# MEMC_Plug_FFC.net
KiCad netlist of a schematic drawn in Altium Designer
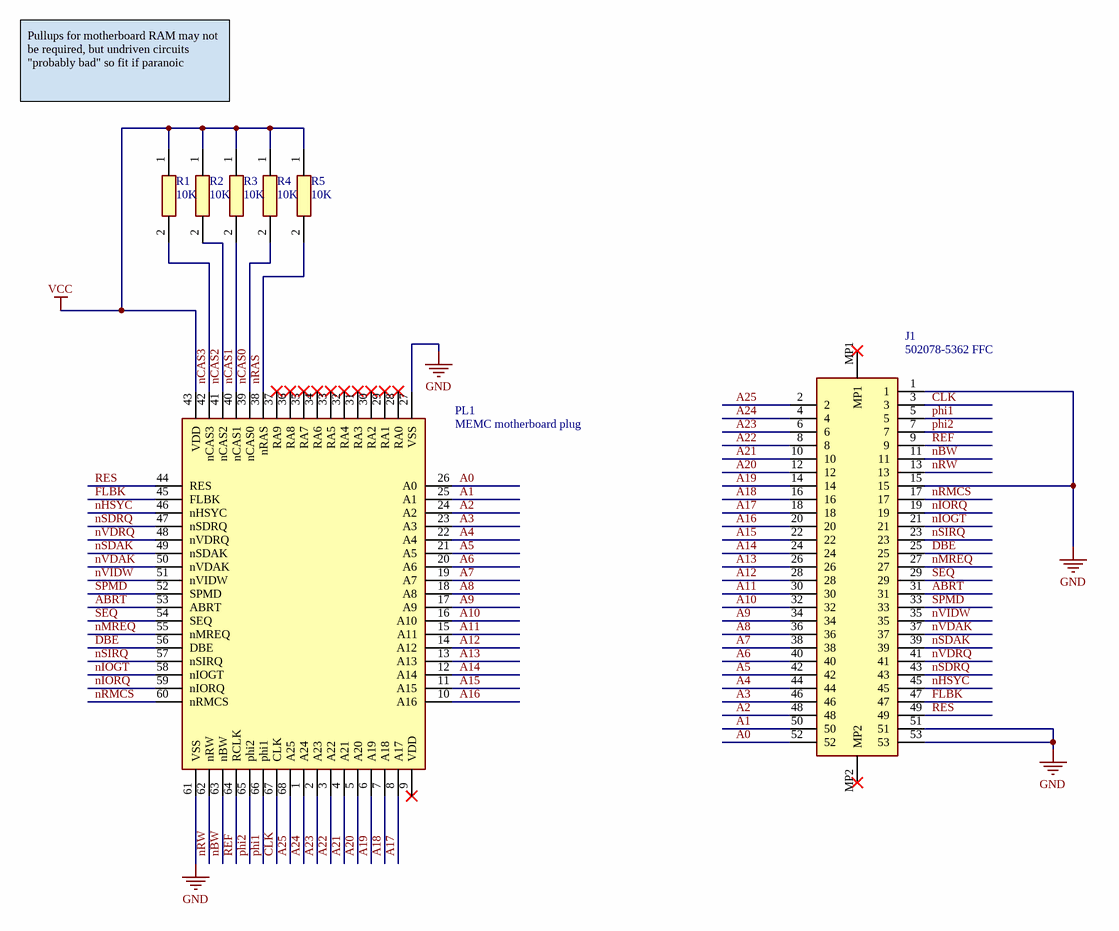
[diagram p0: MEMC_Plug_FFC.SchDoc]

(export (version "E")
  (design (tool "Eeschema 10.0.6"))
  (components
    (comp (ref "J1")
      (value "502078-5362 FFC")
      (footprint "SamacSys:5020785362")
      (description "Connector")
      (fields
        (field (name "MANUFACTURER_PART_NUMBER") "502078-5362")
        (field (name "MOUSER PART NUMBER") "538-502078-5362")
      )
      (libsource (lib "*") (part "502078-5362"))
    )
    (comp (ref "PL1")
      (value "MEMC motherboard plug")
      (footprint "MEMC_Plug")
      (description "MEMC plug")
      (libsource (lib "Acorn") (part "MEMC_Plug"))
    )
    (comp (ref "R1")
      (value "10K")
      (footprint "SamacSys:RESC1005X40N")
      (description "Resistor")
      (fields
        (field (name "MANUFACTURER_PART_NUMBER") "CRCW040210K0FKEDHP")
        (field (name "MOUSER PART NUMBER") "71-CRCW040210K0FKEDH")
      )
      (libsource (lib "*") (part "CRCW040210K0FKEDHP"))
    )
    (comp (ref "R2")
      (value "10K")
      (footprint "SamacSys:RESC1005X40N")
      (description "Resistor")
      (fields
        (field (name "MANUFACTURER_PART_NUMBER") "CRCW040210K0FKEDHP")
        (field (name "MOUSER PART NUMBER") "71-CRCW040210K0FKEDH")
      )
      (libsource (lib "*") (part "CRCW040210K0FKEDHP"))
    )
    (comp (ref "R3")
      (value "10K")
      (footprint "SamacSys:RESC1005X40N")
      (description "Resistor")
      (fields
        (field (name "MANUFACTURER_PART_NUMBER") "CRCW040210K0FKEDHP")
        (field (name "MOUSER PART NUMBER") "71-CRCW040210K0FKEDH")
      )
      (libsource (lib "*") (part "CRCW040210K0FKEDHP"))
    )
    (comp (ref "R4")
      (value "10K")
      (footprint "SamacSys:RESC1005X40N")
      (description "Resistor")
      (fields
        (field (name "MANUFACTURER_PART_NUMBER") "CRCW040210K0FKEDHP")
        (field (name "MOUSER PART NUMBER") "71-CRCW040210K0FKEDH")
      )
      (libsource (lib "*") (part "CRCW040210K0FKEDHP"))
    )
    (comp (ref "R5")
      (value "10K")
      (footprint "SamacSys:RESC1005X40N")
      (description "Resistor")
      (fields
        (field (name "MANUFACTURER_PART_NUMBER") "CRCW040210K0FKEDHP")
        (field (name "MOUSER PART NUMBER") "71-CRCW040210K0FKEDH")
      )
      (libsource (lib "*") (part "CRCW040210K0FKEDHP"))
    )
  )
  (nets
    (net (code "1") (name "/A0") (class "Default")
      (node (ref "J1") (pin "52") (pinfunction "52_52") (pintype "passive"))
      (node (ref "PL1") (pin "26") (pinfunction "A0_26") (pintype "passive"))
    )
    (net (code "2") (name "/A1") (class "Default")
      (node (ref "J1") (pin "50") (pinfunction "50_50") (pintype "passive"))
      (node (ref "PL1") (pin "25") (pinfunction "A1_25") (pintype "passive"))
    )
    (net (code "3") (name "/A2") (class "Default")
      (node (ref "J1") (pin "48") (pinfunction "48_48") (pintype "passive"))
      (node (ref "PL1") (pin "24") (pinfunction "A2_24") (pintype "passive"))
    )
    (net (code "4") (name "/A3") (class "Default")
      (node (ref "J1") (pin "46") (pinfunction "46_46") (pintype "passive"))
      (node (ref "PL1") (pin "23") (pinfunction "A3_23") (pintype "passive"))
    )
    (net (code "5") (name "/A4") (class "Default")
      (node (ref "J1") (pin "44") (pinfunction "44_44") (pintype "passive"))
      (node (ref "PL1") (pin "22") (pinfunction "A4_22") (pintype "passive"))
    )
    (net (code "6") (name "/A5") (class "Default")
      (node (ref "J1") (pin "42") (pinfunction "42_42") (pintype "passive"))
      (node (ref "PL1") (pin "21") (pinfunction "A5_21") (pintype "passive"))
    )
    (net (code "7") (name "/A6") (class "Default")
      (node (ref "J1") (pin "40") (pinfunction "40_40") (pintype "passive"))
      (node (ref "PL1") (pin "20") (pinfunction "A6_20") (pintype "passive"))
    )
    (net (code "8") (name "/A7") (class "Default")
      (node (ref "J1") (pin "38") (pinfunction "38_38") (pintype "passive"))
      (node (ref "PL1") (pin "19") (pinfunction "A7_19") (pintype "passive"))
    )
    (net (code "9") (name "/A8") (class "Default")
      (node (ref "J1") (pin "36") (pinfunction "36_36") (pintype "passive"))
      (node (ref "PL1") (pin "18") (pinfunction "A8_18") (pintype "passive"))
    )
    (net (code "10") (name "/A9") (class "Default")
      (node (ref "J1") (pin "34") (pinfunction "34_34") (pintype "passive"))
      (node (ref "PL1") (pin "17") (pinfunction "A9_17") (pintype "passive"))
    )
    (net (code "11") (name "/A10") (class "Default")
      (node (ref "J1") (pin "32") (pinfunction "32_32") (pintype "passive"))
      (node (ref "PL1") (pin "16") (pinfunction "A10_16") (pintype "passive"))
    )
    (net (code "12") (name "/A11") (class "Default")
      (node (ref "J1") (pin "30") (pinfunction "30_30") (pintype "passive"))
      (node (ref "PL1") (pin "15") (pinfunction "A11_15") (pintype "passive"))
    )
    (net (code "13") (name "/A12") (class "Default")
      (node (ref "J1") (pin "28") (pinfunction "28_28") (pintype "passive"))
      (node (ref "PL1") (pin "14") (pinfunction "A12_14") (pintype "passive"))
    )
    (net (code "14") (name "/A13") (class "Default")
      (node (ref "J1") (pin "26") (pinfunction "26_26") (pintype "passive"))
      (node (ref "PL1") (pin "13") (pinfunction "A13_13") (pintype "passive"))
    )
    (net (code "15") (name "/A14") (class "Default")
      (node (ref "J1") (pin "24") (pinfunction "24_24") (pintype "passive"))
      (node (ref "PL1") (pin "12") (pinfunction "A14_12") (pintype "passive"))
    )
    (net (code "16") (name "/A15") (class "Default")
      (node (ref "J1") (pin "22") (pinfunction "22_22") (pintype "passive"))
      (node (ref "PL1") (pin "11") (pinfunction "A15_11") (pintype "passive"))
    )
    (net (code "17") (name "/A16") (class "Default")
      (node (ref "J1") (pin "20") (pinfunction "20_20") (pintype "passive"))
      (node (ref "PL1") (pin "10") (pinfunction "A16_10") (pintype "passive"))
    )
    (net (code "18") (name "/A17") (class "Default")
      (node (ref "J1") (pin "18") (pinfunction "18_18") (pintype "passive"))
      (node (ref "PL1") (pin "8") (pinfunction "A17_8") (pintype "passive"))
    )
    (net (code "19") (name "/A18") (class "Default")
      (node (ref "J1") (pin "16") (pinfunction "16_16") (pintype "passive"))
      (node (ref "PL1") (pin "7") (pinfunction "A18_7") (pintype "passive"))
    )
    (net (code "20") (name "/A19") (class "Default")
      (node (ref "J1") (pin "14") (pinfunction "14_14") (pintype "passive"))
      (node (ref "PL1") (pin "6") (pinfunction "A19_6") (pintype "passive"))
    )
    (net (code "21") (name "/A20") (class "Default")
      (node (ref "J1") (pin "12") (pinfunction "12_12") (pintype "passive"))
      (node (ref "PL1") (pin "5") (pinfunction "A20_5") (pintype "passive"))
    )
    (net (code "22") (name "/A21") (class "Default")
      (node (ref "J1") (pin "10") (pinfunction "10_10") (pintype "passive"))
      (node (ref "PL1") (pin "4") (pinfunction "A21_4") (pintype "passive"))
    )
    (net (code "23") (name "/A22") (class "Default")
      (node (ref "J1") (pin "8") (pinfunction "8_8") (pintype "passive"))
      (node (ref "PL1") (pin "3") (pinfunction "A22_3") (pintype "passive"))
    )
    (net (code "24") (name "/A23") (class "Default")
      (node (ref "J1") (pin "6") (pinfunction "6_6") (pintype "passive"))
      (node (ref "PL1") (pin "2") (pinfunction "A23_2") (pintype "passive"))
    )
    (net (code "25") (name "/A24") (class "Default")
      (node (ref "J1") (pin "4") (pinfunction "4_4") (pintype "passive"))
      (node (ref "PL1") (pin "1") (pinfunction "A24_1") (pintype "passive"))
    )
    (net (code "26") (name "/A25") (class "Default")
      (node (ref "J1") (pin "2") (pinfunction "2_2") (pintype "passive"))
      (node (ref "PL1") (pin "68") (pinfunction "A25_68") (pintype "passive"))
    )
    (net (code "27") (name "/ABRT") (class "Default")
      (node (ref "J1") (pin "31") (pinfunction "31_31") (pintype "passive"))
      (node (ref "PL1") (pin "53") (pinfunction "ABRT_53") (pintype "passive"))
    )
    (net (code "28") (name "/CLK") (class "Default")
      (node (ref "J1") (pin "3") (pinfunction "3_3") (pintype "passive"))
      (node (ref "PL1") (pin "67") (pinfunction "CLK_67") (pintype "passive"))
    )
    (net (code "29") (name "/DBE") (class "Default")
      (node (ref "J1") (pin "25") (pinfunction "25_25") (pintype "passive"))
      (node (ref "PL1") (pin "56") (pinfunction "DBE_56") (pintype "passive"))
    )
    (net (code "30") (name "/FLBK") (class "Default")
      (node (ref "J1") (pin "47") (pinfunction "47_47") (pintype "passive"))
      (node (ref "PL1") (pin "45") (pinfunction "FLBK_45") (pintype "passive"))
    )
    (net (code "31") (name "/REF") (class "Default")
      (node (ref "J1") (pin "9") (pinfunction "9_9") (pintype "passive"))
      (node (ref "PL1") (pin "64") (pinfunction "RCLK_64") (pintype "passive"))
    )
    (net (code "32") (name "/RES") (class "Default")
      (node (ref "J1") (pin "49") (pinfunction "49_49") (pintype "passive"))
      (node (ref "PL1") (pin "44") (pinfunction "RES_44") (pintype "passive"))
    )
    (net (code "33") (name "/SEQ") (class "Default")
      (node (ref "J1") (pin "29") (pinfunction "29_29") (pintype "passive"))
      (node (ref "PL1") (pin "54") (pinfunction "SEQ_54") (pintype "passive"))
    )
    (net (code "34") (name "/SPMD") (class "Default")
      (node (ref "J1") (pin "33") (pinfunction "33_33") (pintype "passive"))
      (node (ref "PL1") (pin "52") (pinfunction "SPMD_52") (pintype "passive"))
    )
    (net (code "35") (name "/nBW") (class "Default")
      (node (ref "J1") (pin "11") (pinfunction "11_11") (pintype "passive"))
      (node (ref "PL1") (pin "63") (pinfunction "nBW_63") (pintype "passive"))
    )
    (net (code "36") (name "/nCAS0") (class "Default")
      (node (ref "PL1") (pin "39") (pinfunction "nCAS0_39") (pintype "passive"))
      (node (ref "R4") (pin "2") (pinfunction "2_2") (pintype "passive"))
    )
    (net (code "37") (name "/nCAS1") (class "Default")
      (node (ref "PL1") (pin "40") (pinfunction "nCAS1_40") (pintype "passive"))
      (node (ref "R3") (pin "2") (pinfunction "2_2") (pintype "passive"))
    )
    (net (code "38") (name "/nCAS2") (class "Default")
      (node (ref "PL1") (pin "41") (pinfunction "nCAS2_41") (pintype "passive"))
      (node (ref "R2") (pin "2") (pinfunction "2_2") (pintype "passive"))
    )
    (net (code "39") (name "/nCAS3") (class "Default")
      (node (ref "PL1") (pin "42") (pinfunction "nCAS3_42") (pintype "passive"))
      (node (ref "R1") (pin "2") (pinfunction "2_2") (pintype "passive"))
    )
    (net (code "40") (name "/nHSYC") (class "Default")
      (node (ref "J1") (pin "45") (pinfunction "45_45") (pintype "passive"))
      (node (ref "PL1") (pin "46") (pinfunction "nHSYC_46") (pintype "passive"))
    )
    (net (code "41") (name "/nIOGT") (class "Default")
      (node (ref "J1") (pin "21") (pinfunction "21_21") (pintype "passive"))
      (node (ref "PL1") (pin "58") (pinfunction "nIOGT_58") (pintype "passive"))
    )
    (net (code "42") (name "/nIORQ") (class "Default")
      (node (ref "J1") (pin "19") (pinfunction "19_19") (pintype "passive"))
      (node (ref "PL1") (pin "59") (pinfunction "nIORQ_59") (pintype "passive"))
    )
    (net (code "43") (name "/nMREQ") (class "Default")
      (node (ref "J1") (pin "27") (pinfunction "27_27") (pintype "passive"))
      (node (ref "PL1") (pin "55") (pinfunction "nMREQ_55") (pintype "passive"))
    )
    (net (code "44") (name "/nRAS") (class "Default")
      (node (ref "PL1") (pin "38") (pinfunction "nRAS_38") (pintype "passive"))
      (node (ref "R5") (pin "2") (pinfunction "2_2") (pintype "passive"))
    )
    (net (code "45") (name "/nRMCS") (class "Default")
      (node (ref "J1") (pin "17") (pinfunction "17_17") (pintype "passive"))
      (node (ref "PL1") (pin "60") (pinfunction "nRMCS_60") (pintype "passive"))
    )
    (net (code "46") (name "/nRW") (class "Default")
      (node (ref "J1") (pin "13") (pinfunction "13_13") (pintype "passive"))
      (node (ref "PL1") (pin "62") (pinfunction "nRW_62") (pintype "passive"))
    )
    (net (code "47") (name "/nSDAK") (class "Default")
      (node (ref "J1") (pin "39") (pinfunction "39_39") (pintype "passive"))
      (node (ref "PL1") (pin "49") (pinfunction "nSDAK_49") (pintype "passive"))
    )
    (net (code "48") (name "/nSDRQ") (class "Default")
      (node (ref "J1") (pin "43") (pinfunction "43_43") (pintype "passive"))
      (node (ref "PL1") (pin "47") (pinfunction "nSDRQ_47") (pintype "passive"))
    )
    (net (code "49") (name "/nSIRQ") (class "Default")
      (node (ref "J1") (pin "23") (pinfunction "23_23") (pintype "passive"))
      (node (ref "PL1") (pin "57") (pinfunction "nSIRQ_57") (pintype "passive"))
    )
    (net (code "50") (name "/nVDAK") (class "Default")
      (node (ref "J1") (pin "37") (pinfunction "37_37") (pintype "passive"))
      (node (ref "PL1") (pin "50") (pinfunction "nVDAK_50") (pintype "passive"))
    )
    (net (code "51") (name "/nVDRQ") (class "Default")
      (node (ref "J1") (pin "41") (pinfunction "41_41") (pintype "passive"))
      (node (ref "PL1") (pin "48") (pinfunction "nVDRQ_48") (pintype "passive"))
    )
    (net (code "52") (name "/nVIDW") (class "Default")
      (node (ref "J1") (pin "35") (pinfunction "35_35") (pintype "passive"))
      (node (ref "PL1") (pin "51") (pinfunction "nVIDW_51") (pintype "passive"))
    )
    (net (code "53") (name "/phi1") (class "Default")
      (node (ref "J1") (pin "5") (pinfunction "5_5") (pintype "passive"))
      (node (ref "PL1") (pin "66") (pinfunction "phi1_66") (pintype "passive"))
    )
    (net (code "54") (name "/phi2") (class "Default")
      (node (ref "J1") (pin "7") (pinfunction "7_7") (pintype "passive"))
      (node (ref "PL1") (pin "65") (pinfunction "phi2_65") (pintype "passive"))
    )
    (net (code "55") (name "GND") (class "Default")
      (node (ref "J1") (pin "1") (pinfunction "1_1") (pintype "passive"))
      (node (ref "J1") (pin "15") (pinfunction "15_15") (pintype "passive"))
      (node (ref "J1") (pin "51") (pinfunction "51_51") (pintype "passive"))
      (node (ref "J1") (pin "53") (pinfunction "53_53") (pintype "passive"))
      (node (ref "PL1") (pin "27") (pinfunction "VSS_27") (pintype "passive"))
      (node (ref "PL1") (pin "61") (pinfunction "VSS_61") (pintype "passive"))
    )
    (net (code "56") (name "VCC") (class "Default")
      (node (ref "PL1") (pin "43") (pinfunction "VDD_43") (pintype "passive"))
      (node (ref "R1") (pin "1") (pinfunction "1_1") (pintype "passive"))
      (node (ref "R2") (pin "1") (pinfunction "1_1") (pintype "passive"))
      (node (ref "R3") (pin "1") (pinfunction "1_1") (pintype "passive"))
      (node (ref "R4") (pin "1") (pinfunction "1_1") (pintype "passive"))
      (node (ref "R5") (pin "1") (pinfunction "1_1") (pintype "passive"))
    )
    (net (code "57") (name "unconnected-(J1-PadMP1)") (class "Default")
      (node (ref "J1") (pin "MP1") (pinfunction "MP1_MP1") (pintype "passive+no_connect"))
    )
    (net (code "58") (name "unconnected-(J1-PadMP2)") (class "Default")
      (node (ref "J1") (pin "MP2") (pinfunction "MP2_MP2") (pintype "passive+no_connect"))
    )
    (net (code "59") (name "unconnected-(PL1-RA0-Pad28)") (class "Default")
      (node (ref "PL1") (pin "28") (pinfunction "RA0_28") (pintype "passive+no_connect"))
    )
    (net (code "60") (name "unconnected-(PL1-RA1-Pad29)") (class "Default")
      (node (ref "PL1") (pin "29") (pinfunction "RA1_29") (pintype "passive+no_connect"))
    )
    (net (code "61") (name "unconnected-(PL1-RA2-Pad30)") (class "Default")
      (node (ref "PL1") (pin "30") (pinfunction "RA2_30") (pintype "passive+no_connect"))
    )
    (net (code "62") (name "unconnected-(PL1-RA3-Pad31)") (class "Default")
      (node (ref "PL1") (pin "31") (pinfunction "RA3_31") (pintype "passive+no_connect"))
    )
    (net (code "63") (name "unconnected-(PL1-RA4-Pad32)") (class "Default")
      (node (ref "PL1") (pin "32") (pinfunction "RA4_32") (pintype "passive+no_connect"))
    )
    (net (code "64") (name "unconnected-(PL1-RA5-Pad33)") (class "Default")
      (node (ref "PL1") (pin "33") (pinfunction "RA5_33") (pintype "passive+no_connect"))
    )
    (net (code "65") (name "unconnected-(PL1-RA6-Pad34)") (class "Default")
      (node (ref "PL1") (pin "34") (pinfunction "RA6_34") (pintype "passive+no_connect"))
    )
    (net (code "66") (name "unconnected-(PL1-RA7-Pad35)") (class "Default")
      (node (ref "PL1") (pin "35") (pinfunction "RA7_35") (pintype "passive+no_connect"))
    )
    (net (code "67") (name "unconnected-(PL1-RA8-Pad36)") (class "Default")
      (node (ref "PL1") (pin "36") (pinfunction "RA8_36") (pintype "passive+no_connect"))
    )
    (net (code "68") (name "unconnected-(PL1-RA9-Pad37)") (class "Default")
      (node (ref "PL1") (pin "37") (pinfunction "RA9_37") (pintype "passive+no_connect"))
    )
    (net (code "69") (name "unconnected-(PL1-VDD-Pad9)") (class "Default")
      (node (ref "PL1") (pin "9") (pinfunction "VDD_9") (pintype "passive+no_connect"))
    )
  )
)
